# optoSensor.net
KiCad netlist of a schematic drawn in EAGLE
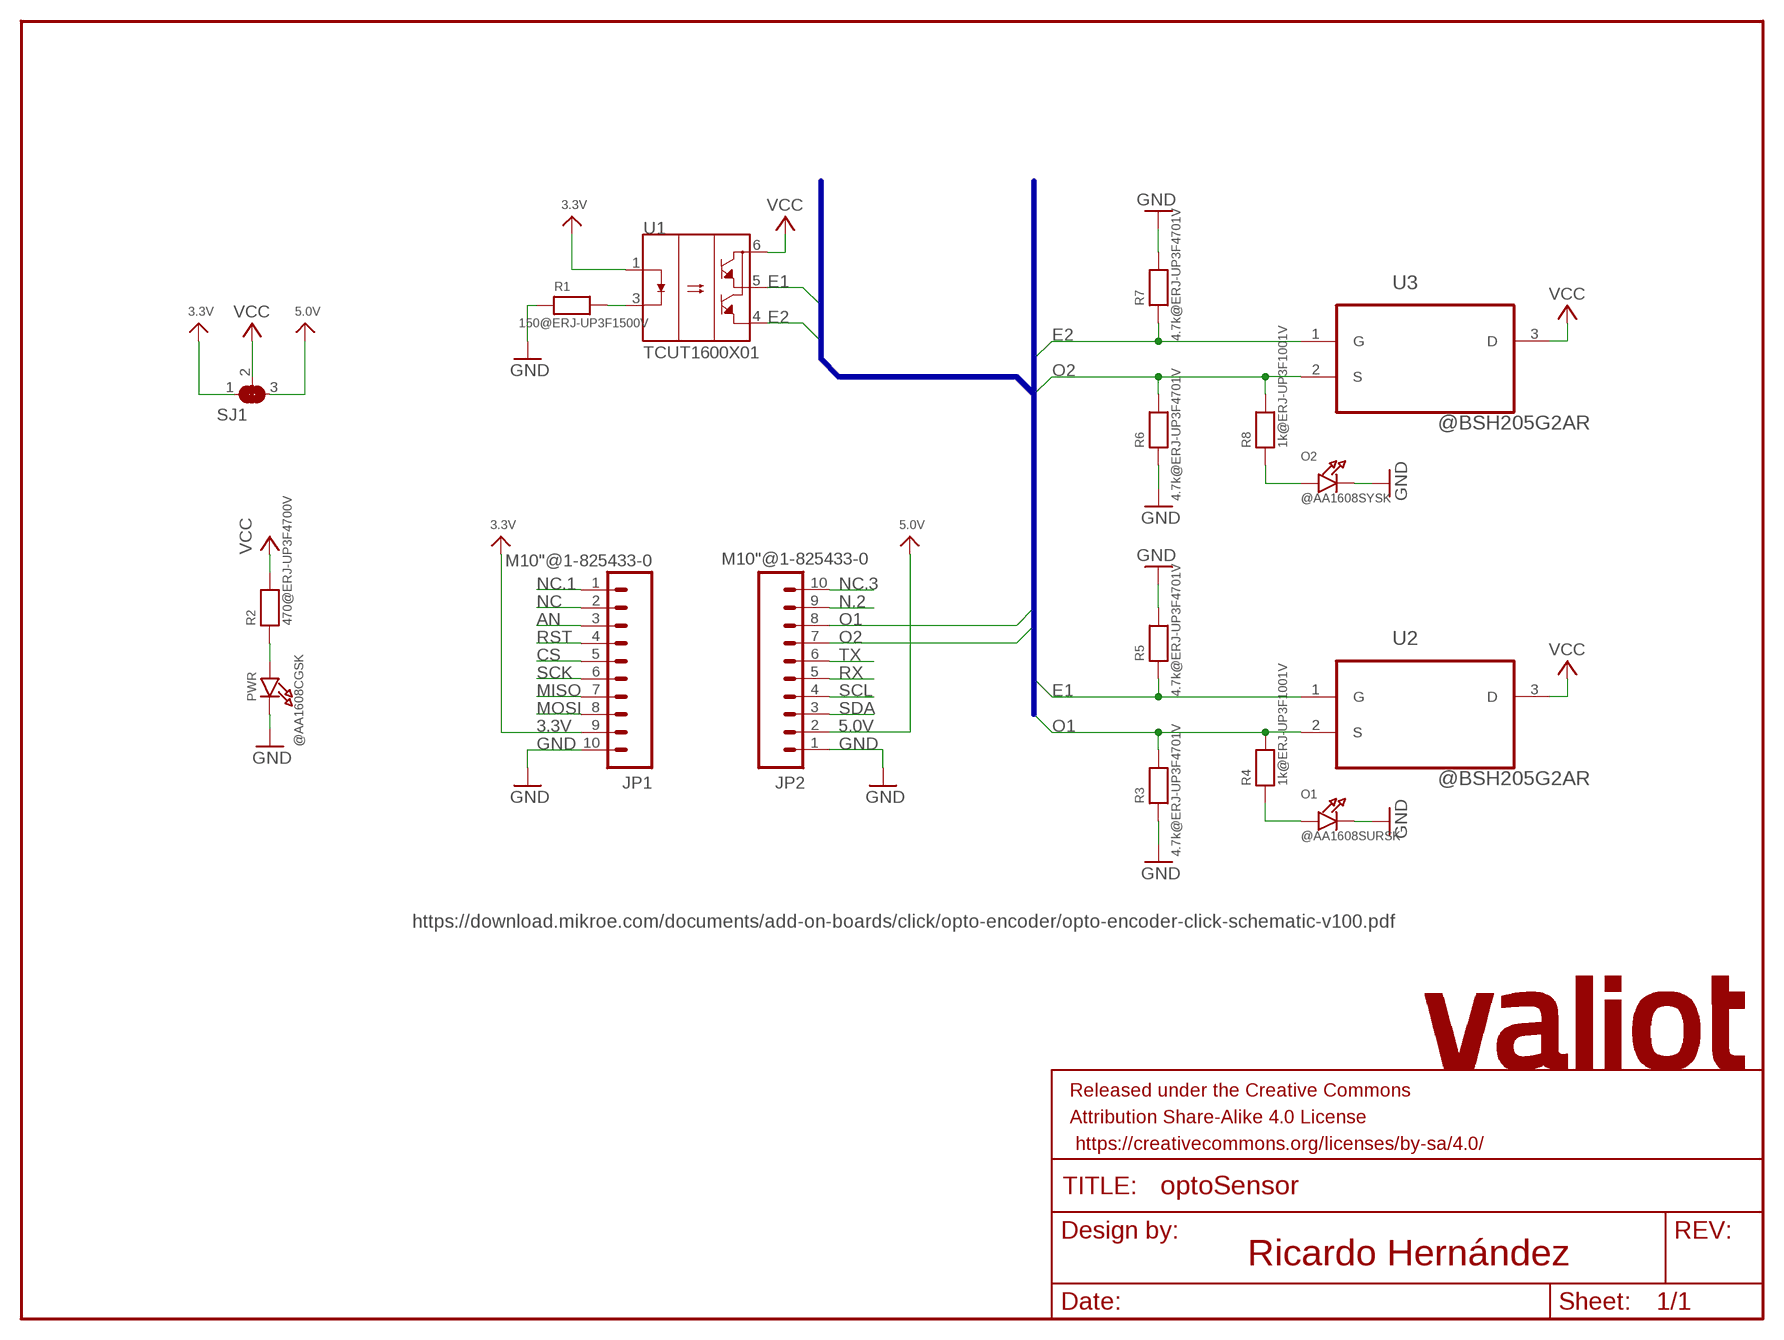
[diagram p0: schematic, sheet 1]

(export (version "E")
  (design (tool "Eeschema 10.0.6"))
  (components
    (comp (ref "FRAME1")
      (value "FRAME-LETTER")
      (footprint "eagle-import:CREATIVE_COMMONS")
      (libsource (lib "eagle-import") (part "FRAME-LETTER"))
    )
    (comp (ref "JP1")
      (value "M10\"@1-825433-0")
      (footprint "eagle-import:1X10")
      (libsource (lib "eagle-import") (part "M10{dblquote}"))
    )
    (comp (ref "JP2")
      (value "M10\"@1-825433-0")
      (footprint "eagle-import:1X10")
      (libsource (lib "eagle-import") (part "M10{dblquote}"))
    )
    (comp (ref "O1")
      (value "@AA1608SURSK")
      (footprint "eagle-import:CHIPLED_0603_NOOUTLINE")
      (libsource (lib "eagle-import") (part "LED0603_NOOUTLINE"))
    )
    (comp (ref "O2")
      (value "@AA1608SYSK")
      (footprint "eagle-import:CHIPLED_0603_NOOUTLINE")
      (libsource (lib "eagle-import") (part "LED0603_NOOUTLINE"))
    )
    (comp (ref "PWR")
      (value "@AA1608CGSK")
      (footprint "eagle-import:CHIPLED_0603_NOOUTLINE")
      (libsource (lib "eagle-import") (part "LED0603_NOOUTLINE"))
    )
    (comp (ref "R1")
      (value "150@ERJ-UP3F1500V")
      (footprint "eagle-import:0603")
      (libsource (lib "eagle-import") (part "RESISTOR0603"))
    )
    (comp (ref "R2")
      (value "470@ERJ-UP3F4700V")
      (footprint "eagle-import:0603")
      (libsource (lib "eagle-import") (part "RESISTOR0603"))
    )
    (comp (ref "R3")
      (value "4.7k@ERJ-UP3F4701V")
      (footprint "eagle-import:0603")
      (libsource (lib "eagle-import") (part "RESISTOR0603"))
    )
    (comp (ref "R4")
      (value "1k@ERJ-UP3F1001V")
      (footprint "eagle-import:0603")
      (libsource (lib "eagle-import") (part "RESISTOR0603"))
    )
    (comp (ref "R5")
      (value "4.7k@ERJ-UP3F4701V")
      (footprint "eagle-import:0603")
      (libsource (lib "eagle-import") (part "RESISTOR0603"))
    )
    (comp (ref "R6")
      (value "4.7k@ERJ-UP3F4701V")
      (footprint "eagle-import:0603")
      (libsource (lib "eagle-import") (part "RESISTOR0603"))
    )
    (comp (ref "R7")
      (value "4.7k@ERJ-UP3F4701V")
      (footprint "eagle-import:0603")
      (libsource (lib "eagle-import") (part "RESISTOR0603"))
    )
    (comp (ref "R8")
      (value "1k@ERJ-UP3F1001V")
      (footprint "eagle-import:0603")
      (libsource (lib "eagle-import") (part "RESISTOR0603"))
    )
    (comp (ref "SJ1")
      (value "SOLDERJUMPER_2WAY0603")
      (footprint "eagle-import:SOLDERJUMPER_2WAY_OPEN_0603")
      (libsource (lib "eagle-import") (part "SOLDERJUMPER_2WAY0603"))
    )
    (comp (ref "U1")
      (value "TCUT1600X01")
      (footprint "eagle-import:XDCR_TCUT1600X01")
      (fields (field (name "MF") "Vishay Semiconductor Opto Division"))
      (libsource (lib "eagle-import") (part "TCUT1600X01"))
    )
    (comp (ref "U2")
      (value "@BSH205G2AR")
      (footprint "eagle-import:SOT103P240X110-3N")
      (fields (field (name "MF") "Diodes Inc.") (field (name "MP") "DMP2305U-7"))
      (libsource (lib "eagle-import") (part "DMP2305U-7"))
    )
    (comp (ref "U3")
      (value "@BSH205G2AR")
      (footprint "eagle-import:SOT103P240X110-3N")
      (fields (field (name "MF") "Diodes Inc.") (field (name "MP") "DMP2305U-7"))
      (libsource (lib "eagle-import") (part "DMP2305U-7"))
    )
  )
  (nets
    (net (code "1") (name "/AN") (class "Default")
      (node (ref "JP1") (pin "3") (pinfunction "3_3") (pintype "passive"))
    )
    (net (code "2") (name "/CS") (class "Default")
      (node (ref "JP1") (pin "5") (pinfunction "5_5") (pintype "passive"))
    )
    (net (code "3") (name "/E1") (class "Default")
      (node (ref "R5") (pin "1") (pinfunction "1_1") (pintype "passive"))
      (node (ref "U1") (pin "5") (pinfunction "E1_5") (pintype "passive"))
      (node (ref "U2") (pin "1") (pinfunction "G_1") (pintype "input"))
    )
    (net (code "4") (name "/E2") (class "Default")
      (node (ref "R7") (pin "1") (pinfunction "1_1") (pintype "passive"))
      (node (ref "U1") (pin "4") (pinfunction "E2_4") (pintype "passive"))
      (node (ref "U3") (pin "1") (pinfunction "G_1") (pintype "input"))
    )
    (net (code "5") (name "/MISO") (class "Default")
      (node (ref "JP1") (pin "7") (pinfunction "7_7") (pintype "passive"))
    )
    (net (code "6") (name "/MOSI") (class "Default")
      (node (ref "JP1") (pin "8") (pinfunction "8_8") (pintype "passive"))
    )
    (net (code "7") (name "/N.2") (class "Default")
      (node (ref "JP2") (pin "9") (pinfunction "9_9") (pintype "passive"))
    )
    (net (code "8") (name "/NC") (class "Default")
      (node (ref "JP1") (pin "2") (pinfunction "2_2") (pintype "passive"))
    )
    (net (code "9") (name "/NC.1") (class "Default")
      (node (ref "JP1") (pin "1") (pinfunction "1_1") (pintype "passive"))
    )
    (net (code "10") (name "/NC.3") (class "Default")
      (node (ref "JP2") (pin "10") (pinfunction "10_10") (pintype "passive"))
    )
    (net (code "11") (name "/O1") (class "Default")
      (node (ref "JP2") (pin "8") (pinfunction "8_8") (pintype "passive"))
      (node (ref "R3") (pin "2") (pinfunction "2_2") (pintype "passive"))
      (node (ref "R4") (pin "2") (pinfunction "2_2") (pintype "passive"))
      (node (ref "U2") (pin "2") (pinfunction "S_2") (pintype "passive"))
    )
    (net (code "12") (name "/O2") (class "Default")
      (node (ref "JP2") (pin "7") (pinfunction "7_7") (pintype "passive"))
      (node (ref "R6") (pin "2") (pinfunction "2_2") (pintype "passive"))
      (node (ref "R8") (pin "2") (pinfunction "2_2") (pintype "passive"))
      (node (ref "U3") (pin "2") (pinfunction "S_2") (pintype "passive"))
    )
    (net (code "13") (name "/RST") (class "Default")
      (node (ref "JP1") (pin "4") (pinfunction "4_4") (pintype "passive"))
    )
    (net (code "14") (name "/RX") (class "Default")
      (node (ref "JP2") (pin "5") (pinfunction "5_5") (pintype "passive"))
    )
    (net (code "15") (name "/SCK") (class "Default")
      (node (ref "JP1") (pin "6") (pinfunction "6_6") (pintype "passive"))
    )
    (net (code "16") (name "/SCL") (class "Default")
      (node (ref "JP2") (pin "4") (pinfunction "4_4") (pintype "passive"))
    )
    (net (code "17") (name "/SDA") (class "Default")
      (node (ref "JP2") (pin "3") (pinfunction "3_3") (pintype "passive"))
    )
    (net (code "18") (name "/TX") (class "Default")
      (node (ref "JP2") (pin "6") (pinfunction "6_6") (pintype "passive"))
    )
    (net (code "19") (name "3.3V") (class "Default")
      (node (ref "JP1") (pin "9") (pinfunction "9_9") (pintype "passive"))
      (node (ref "SJ1") (pin "1") (pinfunction "1_1") (pintype "passive"))
      (node (ref "U1") (pin "1") (pinfunction "A_1") (pintype "passive"))
    )
    (net (code "20") (name "5.0V") (class "Default")
      (node (ref "JP2") (pin "2") (pinfunction "2_2") (pintype "passive"))
      (node (ref "SJ1") (pin "3") (pinfunction "3_3") (pintype "passive"))
    )
    (net (code "21") (name "GND") (class "Default")
      (node (ref "JP1") (pin "10") (pinfunction "10_10") (pintype "passive"))
      (node (ref "JP2") (pin "1") (pinfunction "1_1") (pintype "passive"))
      (node (ref "O1") (pin "C") (pinfunction "C_C") (pintype "passive"))
      (node (ref "O2") (pin "C") (pinfunction "C_C") (pintype "passive"))
      (node (ref "PWR") (pin "C") (pinfunction "C_C") (pintype "passive"))
      (node (ref "R1") (pin "1") (pinfunction "1_1") (pintype "passive"))
      (node (ref "R3") (pin "1") (pinfunction "1_1") (pintype "passive"))
      (node (ref "R5") (pin "2") (pinfunction "2_2") (pintype "passive"))
      (node (ref "R6") (pin "1") (pinfunction "1_1") (pintype "passive"))
      (node (ref "R7") (pin "2") (pinfunction "2_2") (pintype "passive"))
    )
    (net (code "22") (name "Net-(O1-PadA)") (class "Default")
      (node (ref "O1") (pin "A") (pinfunction "A_A") (pintype "passive"))
      (node (ref "R4") (pin "1") (pinfunction "1_1") (pintype "passive"))
    )
    (net (code "23") (name "Net-(O2-PadA)") (class "Default")
      (node (ref "O2") (pin "A") (pinfunction "A_A") (pintype "passive"))
      (node (ref "R8") (pin "1") (pinfunction "1_1") (pintype "passive"))
    )
    (net (code "24") (name "Net-(PWR-PadA)") (class "Default")
      (node (ref "PWR") (pin "A") (pinfunction "A_A") (pintype "passive"))
      (node (ref "R2") (pin "1") (pinfunction "1_1") (pintype "passive"))
    )
    (net (code "25") (name "Net-(U1-CATH)") (class "Default")
      (node (ref "R1") (pin "2") (pinfunction "2_2") (pintype "passive"))
      (node (ref "U1") (pin "3") (pinfunction "CATH_3") (pintype "passive"))
    )
    (net (code "26") (name "VCC") (class "Default")
      (node (ref "R2") (pin "2") (pinfunction "2_2") (pintype "passive"))
      (node (ref "SJ1") (pin "2") (pinfunction "2_2") (pintype "passive"))
      (node (ref "U1") (pin "6") (pinfunction "COLL_6") (pintype "passive"))
      (node (ref "U2") (pin "3") (pinfunction "D_3") (pintype "output"))
      (node (ref "U3") (pin "3") (pinfunction "D_3") (pintype "output"))
    )
  )
)
